# FanControl.net
KiCad netlist of a schematic drawn in Altium Designer
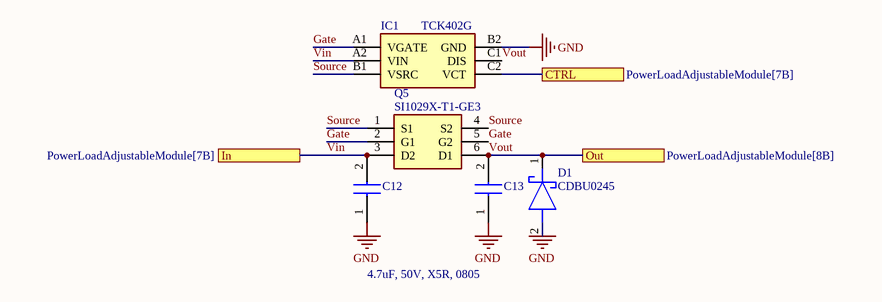
[diagram p0: FanControl.SchDoc]

(export (version "E")
  (design (tool "Eeschema 10.0.6"))
  (components
    (comp (ref "C12")
      (value "4.7uF, 50V, X5R, 0805")
      (footprint "SamacSys:CAPC2012X145N")
      (description "Capacitor")
      (fields
        (field (name "MANUFACTURER_PART_NUMBER") "GRM21BR61H475ME51L")
        (field (name "MOUSER PART NUMBER") "81-GRM21BR61H475M51L")
      )
      (libsource (lib "*") (part "GRM21BR61H475ME51L"))
    )
    (comp (ref "C13")
      (value "4.7uF, 50V, X5R, 0805")
      (footprint "SamacSys:CAPC2012X145N")
      (description "Capacitor")
      (fields
        (field (name "MANUFACTURER_PART_NUMBER") "GRM21BR61H475ME51L")
        (field (name "MOUSER PART NUMBER") "81-GRM21BR61H475M51L")
      )
      (libsource (lib "*") (part "GRM21BR61H475ME51L"))
    )
    (comp (ref "D1")
      (value "CDBU0245")
      (footprint "SamacSys:DIOC1709X85N")
      (description "Schottky Diode")
      (fields (field (name "MOUSER PART NUMBER") "750-CDBU0245"))
      (libsource (lib "*") (part "CDBU0245"))
    )
    (comp (ref "IC1")
      (value "TCK402G")
      (footprint "SamacSys:BGA6C40P2X3_80X120X59")
      (description "Integrated Circuit")
      (libsource (lib "*") (part "TCK402G"))
    )
    (comp (ref "Q5")
      (value "SI1029X-T1-GE3")
      (footprint "SamacSys:SOTFL50P160X60-6N")
      (description "Transistor")
      (fields (field (name "MOUSER PART NUMBER") "781-SI1029X-T1-GE3"))
      (libsource (lib "*") (part "SI1029X-T1-GE3"))
    )
  )
  (nets
    (net (code "1") (name "/CTRL") (class "Default")
      (node (ref "IC1") (pin "C2") (pinfunction "VCT_C2") (pintype "passive"))
    )
    (net (code "2") (name "/Gate") (class "Default")
      (node (ref "IC1") (pin "A1") (pinfunction "VGATE_A1") (pintype "passive"))
      (node (ref "Q5") (pin "2") (pinfunction "G1_2") (pintype "passive"))
      (node (ref "Q5") (pin "5") (pinfunction "G2_5") (pintype "passive"))
    )
    (net (code "3") (name "/Source") (class "Default")
      (node (ref "IC1") (pin "B1") (pinfunction "VSRC_B1") (pintype "passive"))
      (node (ref "Q5") (pin "1") (pinfunction "S1_1") (pintype "passive"))
      (node (ref "Q5") (pin "4") (pinfunction "S2_4") (pintype "passive"))
    )
    (net (code "4") (name "/Vin") (class "Default")
      (node (ref "C12") (pin "2") (pinfunction "2_2") (pintype "passive"))
      (node (ref "IC1") (pin "A2") (pinfunction "VIN_A2") (pintype "passive"))
      (node (ref "Q5") (pin "3") (pinfunction "D2_3") (pintype "passive"))
    )
    (net (code "5") (name "/Vout") (class "Default")
      (node (ref "C13") (pin "2") (pinfunction "2_2") (pintype "passive"))
      (node (ref "D1") (pin "1") (pinfunction "K_1") (pintype "passive"))
      (node (ref "IC1") (pin "C1") (pinfunction "DIS_C1") (pintype "passive"))
      (node (ref "Q5") (pin "6") (pinfunction "D1_6") (pintype "passive"))
    )
    (net (code "6") (name "GND") (class "Default")
      (node (ref "C12") (pin "1") (pinfunction "1_1") (pintype "passive"))
      (node (ref "C13") (pin "1") (pinfunction "1_1") (pintype "passive"))
      (node (ref "D1") (pin "2") (pinfunction "A_2") (pintype "passive"))
      (node (ref "IC1") (pin "B2") (pinfunction "GND_B2") (pintype "passive"))
    )
  )
)
